# System.net
KiCad netlist of a schematic drawn in Altium Designer
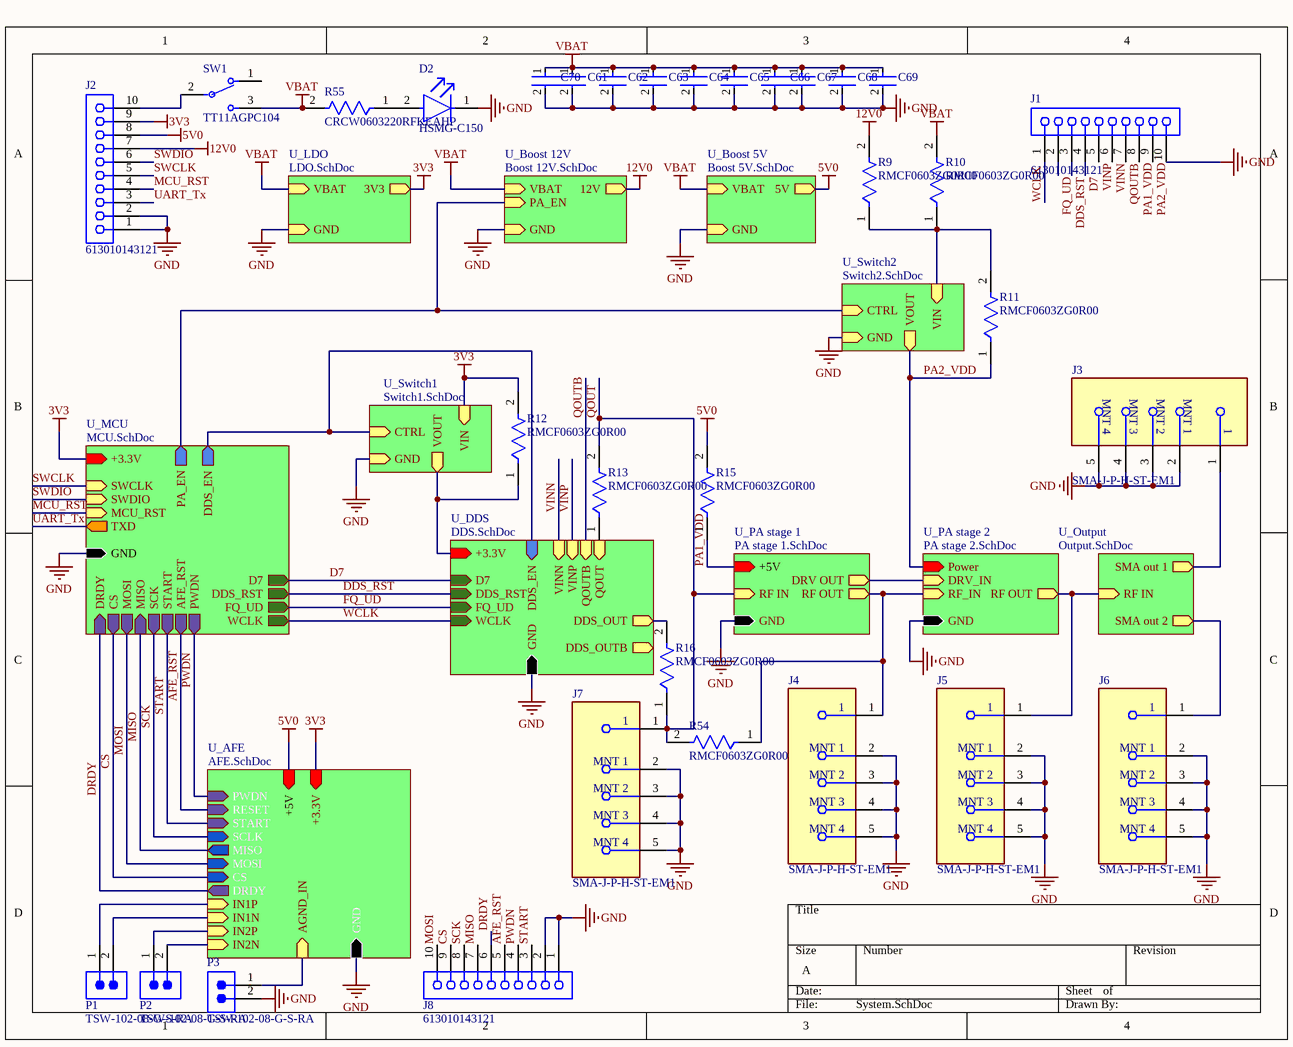
[diagram p0: System.SchDoc]

(export (version "E")
  (design (tool "Eeschema 10.0.6"))
  (components
    (comp (ref "C61")
      (value "GRM21BR60J107ME15K")
      (footprint "FP-GRM21B-0_2-e0_2_0_7-IPC_B")
      (description "Chip Multilayer Ceramic Capacitors for General Purpose, 0805, 100uF, X5R, 15%, 20%, 6.3V")
      (fields (field (name "TOLERANCE") "20%"))
      (libsource (lib "Altium Content Vault") (part "b4654b650e69147ec39a6b967a45e02"))
    )
    (comp (ref "C62")
      (value "GRM21BR60J107ME15K")
      (footprint "FP-GRM21B-0_2-e0_2_0_7-IPC_B")
      (description "Chip Multilayer Ceramic Capacitors for General Purpose, 0805, 100uF, X5R, 15%, 20%, 6.3V")
      (fields (field (name "TOLERANCE") "20%"))
      (libsource (lib "Altium Content Vault") (part "b4654b650e69147ec39a6b967a45e02"))
    )
    (comp (ref "C63")
      (value "GRM21BR60J107ME15K")
      (footprint "FP-GRM21B-0_2-e0_2_0_7-IPC_B")
      (description "Chip Multilayer Ceramic Capacitors for General Purpose, 0805, 100uF, X5R, 15%, 20%, 6.3V")
      (fields (field (name "TOLERANCE") "20%"))
      (libsource (lib "Altium Content Vault") (part "b4654b650e69147ec39a6b967a45e02"))
    )
    (comp (ref "C64")
      (value "GRM21BR60J107ME15K")
      (footprint "FP-GRM21B-0_2-e0_2_0_7-IPC_B")
      (description "Chip Multilayer Ceramic Capacitors for General Purpose, 0805, 100uF, X5R, 15%, 20%, 6.3V")
      (fields (field (name "TOLERANCE") "20%"))
      (libsource (lib "Altium Content Vault") (part "b4654b650e69147ec39a6b967a45e02"))
    )
    (comp (ref "C65")
      (value "GRM21BR60J107ME15K")
      (footprint "FP-GRM21B-0_2-e0_2_0_7-IPC_B")
      (description "Chip Multilayer Ceramic Capacitors for General Purpose, 0805, 100uF, X5R, 15%, 20%, 6.3V")
      (fields (field (name "TOLERANCE") "20%"))
      (libsource (lib "Altium Content Vault") (part "b4654b650e69147ec39a6b967a45e02"))
    )
    (comp (ref "C66")
      (value "GRM21BR60J107ME15K")
      (footprint "FP-GRM21B-0_2-e0_2_0_7-IPC_B")
      (description "Chip Multilayer Ceramic Capacitors for General Purpose, 0805, 100uF, X5R, 15%, 20%, 6.3V")
      (fields (field (name "TOLERANCE") "20%"))
      (libsource (lib "Altium Content Vault") (part "b4654b650e69147ec39a6b967a45e02"))
    )
    (comp (ref "C67")
      (value "GRM21BR60J107ME15K")
      (footprint "FP-GRM21B-0_2-e0_2_0_7-IPC_B")
      (description "Chip Multilayer Ceramic Capacitors for General Purpose, 0805, 100uF, X5R, 15%, 20%, 6.3V")
      (fields (field (name "TOLERANCE") "20%"))
      (libsource (lib "Altium Content Vault") (part "b4654b650e69147ec39a6b967a45e02"))
    )
    (comp (ref "C68")
      (value "GRM21BR60J107ME15K")
      (footprint "FP-GRM21B-0_2-e0_2_0_7-IPC_B")
      (description "Chip Multilayer Ceramic Capacitors for General Purpose, 0805, 100uF, X5R, 15%, 20%, 6.3V")
      (fields (field (name "TOLERANCE") "20%"))
      (libsource (lib "Altium Content Vault") (part "b4654b650e69147ec39a6b967a45e02"))
    )
    (comp (ref "C69")
      (value "GRM21BR60J107ME15K")
      (footprint "FP-GRM21B-0_2-e0_2_0_7-IPC_B")
      (description "Chip Multilayer Ceramic Capacitors for General Purpose, 0805, 100uF, X5R, 15%, 20%, 6.3V")
      (fields (field (name "TOLERANCE") "20%"))
      (libsource (lib "Altium Content Vault") (part "b4654b650e69147ec39a6b967a45e02"))
    )
    (comp (ref "C70")
      (value "GRM21BR60J107ME15K")
      (footprint "FP-GRM21B-0_2-e0_2_0_7-IPC_B")
      (description "Chip Multilayer Ceramic Capacitors for General Purpose, 0805, 100uF, X5R, 15%, 20%, 6.3V")
      (fields (field (name "TOLERANCE") "20%"))
      (libsource (lib "Altium Content Vault") (part "b4654b650e69147ec39a6b967a45e02"))
    )
    (comp (ref "D2")
      (value "HSMG-C150")
      (footprint "FP-HSMG-C150-MFG")
      (description "LED GREEN DIFFUSED 1206 SMD")
      (fields
        (field (name "MANUFACTURER") "Broadcom")
        (field (name "OCTOPART") "https://octopart.com/hsmg-c150-broadcom-71131304")
      )
      (libsource (lib "Altium Content Vault") (part "8706943c75ba83719d021d2fdc84c58"))
    )
    (comp (ref "J1")
      (value "613010143121")
      (footprint "613010143121")
      (libsource (lib "Altium Content Vault") (part "Header_Female_1R_10P"))
    )
    (comp (ref "J2")
      (value "613010143121")
      (footprint "613010143121")
      (libsource (lib "Altium Content Vault") (part "Header_Female_1R_10P"))
    )
    (comp (ref "J3")
      (value "SMA-J-P-H-ST-EM1")
      (footprint "FP-SMA-J-P-H-ST-EM1-MFG")
      (description "CONN SMA JACK STR 50OHM EDGE MNT")
      (libsource (lib "") (part "c65b8a639cdaef1819ea20b5466f8fa_1"))
    )
    (comp (ref "J4")
      (value "SMA-J-P-H-ST-EM1")
      (footprint "FP-SMA-J-P-H-ST-EM1-MFG")
      (description "CONN SMA JACK STR 50OHM EDGE MNT")
      (libsource (lib "Altium Content Vault") (part "c65b8a639cdaef1819ea20b5466f8fa"))
    )
    (comp (ref "J5")
      (value "SMA-J-P-H-ST-EM1")
      (footprint "FP-SMA-J-P-H-ST-EM1-MFG")
      (description "CONN SMA JACK STR 50OHM EDGE MNT")
      (libsource (lib "Altium Content Vault") (part "c65b8a639cdaef1819ea20b5466f8fa"))
    )
    (comp (ref "J6")
      (value "SMA-J-P-H-ST-EM1")
      (footprint "FP-SMA-J-P-H-ST-EM1-MFG")
      (description "CONN SMA JACK STR 50OHM EDGE MNT")
      (libsource (lib "Altium Content Vault") (part "c65b8a639cdaef1819ea20b5466f8fa"))
    )
    (comp (ref "J7")
      (value "SMA-J-P-H-ST-EM1")
      (footprint "FP-SMA-J-P-H-ST-EM1-MFG")
      (description "CONN SMA JACK STR 50OHM EDGE MNT")
      (libsource (lib "Altium Content Vault") (part "c65b8a639cdaef1819ea20b5466f8fa"))
    )
    (comp (ref "J8")
      (value "613010143121")
      (footprint "613010143121")
      (libsource (lib "Altium Content Vault") (part "Header_Female_1R_10P"))
    )
    (comp (ref "P1")
      (value "TSW-102-08-G-S-RA")
      (footprint "SMTC-TSW-102-08-X-S-RA")
      (fields (field (name "MANUFACTURER") "Samtec"))
      (libsource (lib "Altium Content Vault") (part "SMTC-TSW-102-X-X-S-X"))
    )
    (comp (ref "P2")
      (value "TSW-102-08-G-S-RA")
      (footprint "SMTC-TSW-102-08-X-S-RA")
      (fields (field (name "MANUFACTURER") "Samtec"))
      (libsource (lib "Altium Content Vault") (part "SMTC-TSW-102-X-X-S-X"))
    )
    (comp (ref "P3")
      (value "TSW-102-08-G-S-RA")
      (footprint "SMTC-TSW-102-08-X-S-RA")
      (fields (field (name "MANUFACTURER") "Samtec"))
      (libsource (lib "Altium Content Vault") (part "SMTC-TSW-102-X-X-S-X"))
    )
    (comp (ref "R9")
      (value "RMCF0603ZG0R00")
      (footprint "FP-RMCF0603-IPC_B")
      (description "0Ω ±0 0.1W 0603 Thick Film Chip Resistor AEC-Q200 compliant")
      (libsource (lib "Altium Content Vault") (part "1029c3af85768c4190bb7ad29bc67b5"))
    )
    (comp (ref "R10")
      (value "RMCF0603ZG0R00")
      (footprint "FP-RMCF0603-IPC_B")
      (description "0Ω ±0 0.1W 0603 Thick Film Chip Resistor AEC-Q200 compliant")
      (libsource (lib "Altium Content Vault") (part "1029c3af85768c4190bb7ad29bc67b5"))
    )
    (comp (ref "R11")
      (value "RMCF0603ZG0R00")
      (footprint "FP-RMCF0603-IPC_B")
      (description "0Ω ±0 0.1W 0603 Thick Film Chip Resistor AEC-Q200 compliant")
      (libsource (lib "Altium Content Vault") (part "1029c3af85768c4190bb7ad29bc67b5"))
    )
    (comp (ref "R12")
      (value "RMCF0603ZG0R00")
      (footprint "FP-RMCF0603-IPC_B")
      (description "0Ω ±0 0.1W 0603 Thick Film Chip Resistor AEC-Q200 compliant")
      (libsource (lib "Altium Content Vault") (part "1029c3af85768c4190bb7ad29bc67b5"))
    )
    (comp (ref "R13")
      (value "RMCF0603ZG0R00")
      (footprint "FP-RMCF0603-IPC_B")
      (description "0Ω ±0 0.1W 0603 Thick Film Chip Resistor AEC-Q200 compliant")
      (libsource (lib "Altium Content Vault") (part "1029c3af85768c4190bb7ad29bc67b5"))
    )
    (comp (ref "R15")
      (value "RMCF0603ZG0R00")
      (footprint "FP-RMCF0603-IPC_B")
      (description "0Ω ±0 0.1W 0603 Thick Film Chip Resistor AEC-Q200 compliant")
      (libsource (lib "Altium Content Vault") (part "1029c3af85768c4190bb7ad29bc67b5"))
    )
    (comp (ref "R16")
      (value "RMCF0603ZG0R00")
      (footprint "FP-RMCF0603-IPC_B")
      (description "0Ω ±0 0.1W 0603 Thick Film Chip Resistor AEC-Q200 compliant")
      (libsource (lib "Altium Content Vault") (part "1029c3af85768c4190bb7ad29bc67b5"))
    )
    (comp (ref "R54")
      (value "RMCF0603ZG0R00")
      (footprint "FP-RMCF0603-IPC_B")
      (description "0Ω ±0 0.1W 0603 Thick Film Chip Resistor AEC-Q200 compliant")
      (libsource (lib "Altium Content Vault") (part "1029c3af85768c4190bb7ad29bc67b5"))
    )
    (comp (ref "R55")
      (value "CRCW0603220RFKEAHP")
      (footprint "FP-CRCW0603-HPe3-IPC_A")
      (description "RES Thick Film, 220Ω, 1%, 0.33W, 100ppm/°C, 0603")
      (fields (field (name "TOLERANCE") "1%"))
      (libsource (lib "Altium Content Vault") (part "1029c3af85768c4190bb7ad29bc67b5"))
    )
    (comp (ref "SW1")
      (value "TT11AGPC104")
      (footprint "FP-TT11AGPC104-MFG")
      (description "SWITCH TOGGLE SPST 0.4VA 20V")
      (libsource (lib "Altium Content Vault") (part "52c419afdc2a387c7d548259a9aeefb"))
    )
  )
  (nets
    (net (code "1") (name "/AFE_RST") (class "Default")
      (node (ref "J8") (pin "5") (pinfunction "5_5") (pintype "passive"))
    )
    (net (code "2") (name "/AGND_IN") (class "Default")
      (node (ref "P3") (pin "1") (pinfunction "1_1") (pintype "passive"))
    )
    (net (code "3") (name "/CS") (class "Default")
      (node (ref "J8") (pin "9") (pinfunction "9_9") (pintype "passive"))
    )
    (net (code "4") (name "/D7") (class "Default")
      (node (ref "J1") (pin "4") (pinfunction "4_4") (pintype "passive"))
    )
    (net (code "6") (name "/DDS_OUT") (class "Default")
      (node (ref "R16") (pin "2") (pinfunction "2_2") (pintype "passive"))
    )
    (net (code "8") (name "/DDS_RST") (class "Default")
      (node (ref "J1") (pin "3") (pinfunction "3_3") (pintype "passive"))
    )
    (net (code "9") (name "/DRDY") (class "Default")
      (node (ref "J8") (pin "6") (pinfunction "6_6") (pintype "passive"))
    )
    (net (code "11") (name "/FQ_UD") (class "Default")
      (node (ref "J1") (pin "2") (pinfunction "2_2") (pintype "passive"))
    )
    (net (code "12") (name "/IN1N") (class "Default")
      (node (ref "P1") (pin "2") (pinfunction "2_2") (pintype "passive"))
    )
    (net (code "13") (name "/IN1P") (class "Default")
      (node (ref "P1") (pin "1") (pinfunction "1_1") (pintype "passive"))
    )
    (net (code "14") (name "/IN2N") (class "Default")
      (node (ref "P2") (pin "2") (pinfunction "2_2") (pintype "passive"))
    )
    (net (code "15") (name "/IN2P") (class "Default")
      (node (ref "P2") (pin "1") (pinfunction "1_1") (pintype "passive"))
    )
    (net (code "16") (name "/MCU_RST") (class "Default")
      (node (ref "J2") (pin "4") (pinfunction "4_4") (pintype "passive"))
    )
    (net (code "17") (name "/MISO") (class "Default")
      (node (ref "J8") (pin "7") (pinfunction "7_7") (pintype "passive"))
    )
    (net (code "18") (name "/MOSI") (class "Default")
      (node (ref "J8") (pin "10") (pinfunction "10_10") (pintype "passive"))
    )
    (net (code "19") (name "/PA1_VDD") (class "Default")
      (node (ref "J1") (pin "8") (pinfunction "8_8") (pintype "passive"))
      (node (ref "R15") (pin "1") (pinfunction "1_1") (pintype "passive"))
    )
    (net (code "20") (name "/PA2_VDD") (class "Default")
      (node (ref "J1") (pin "9") (pinfunction "9_9") (pintype "passive"))
      (node (ref "R11") (pin "1") (pinfunction "1_1") (pintype "passive"))
    )
    (net (code "22") (name "/PWDN") (class "Default")
      (node (ref "J8") (pin "4") (pinfunction "4_4") (pintype "passive"))
    )
    (net (code "23") (name "/QOUT") (class "Default")
      (node (ref "J7") (pin "1") (pinfunction "1_1") (pintype "passive"))
      (node (ref "R13") (pin "2") (pinfunction "2_2") (pintype "passive"))
      (node (ref "R16") (pin "1") (pinfunction "1_1") (pintype "passive"))
      (node (ref "R54") (pin "2") (pinfunction "2_2") (pintype "passive"))
    )
    (net (code "24") (name "/QOUTB") (class "Default")
      (node (ref "J1") (pin "7") (pinfunction "7_7") (pintype "passive"))
    )
    (net (code "25") (name "/QOUT_1") (class "Default")
      (node (ref "R13") (pin "1") (pinfunction "1_1") (pintype "passive"))
    )
    (net (code "26") (name "/RF OUT") (class "Default")
      (node (ref "J5") (pin "1") (pinfunction "1_1") (pintype "passive"))
    )
    (net (code "27") (name "/RF OUT_1") (class "Default")
      (node (ref "J4") (pin "1") (pinfunction "1_1") (pintype "passive"))
      (node (ref "R54") (pin "1") (pinfunction "1_1") (pintype "passive"))
    )
    (net (code "28") (name "/SCK") (class "Default")
      (node (ref "J8") (pin "8") (pinfunction "8_8") (pintype "passive"))
    )
    (net (code "29") (name "/SMA out 1") (class "Default")
      (node (ref "J3") (pin "1") (pinfunction "1_1") (pintype "passive"))
    )
    (net (code "30") (name "/SMA out 2") (class "Default")
      (node (ref "J6") (pin "1") (pinfunction "1_1") (pintype "passive"))
    )
    (net (code "31") (name "/START") (class "Default")
      (node (ref "J8") (pin "3") (pinfunction "3_3") (pintype "passive"))
    )
    (net (code "32") (name "/SWCLK") (class "Default")
      (node (ref "J2") (pin "5") (pinfunction "5_5") (pintype "passive"))
    )
    (net (code "33") (name "/SWDIO") (class "Default")
      (node (ref "J2") (pin "6") (pinfunction "6_6") (pintype "passive"))
    )
    (net (code "34") (name "/UART_Tx") (class "Default")
      (node (ref "J2") (pin "3") (pinfunction "3_3") (pintype "passive"))
    )
    (net (code "35") (name "/VIN") (class "Default")
      (node (ref "R10") (pin "1") (pinfunction "1_1") (pintype "passive"))
      (node (ref "R11") (pin "2") (pinfunction "2_2") (pintype "passive"))
      (node (ref "R9") (pin "1") (pinfunction "1_1") (pintype "passive"))
    )
    (net (code "36") (name "/VINN") (class "Default")
      (node (ref "J1") (pin "6") (pinfunction "6_6") (pintype "passive"))
    )
    (net (code "37") (name "/VINP") (class "Default")
      (node (ref "J1") (pin "5") (pinfunction "5_5") (pintype "passive"))
    )
    (net (code "38") (name "/VOUT") (class "Default")
      (node (ref "R12") (pin "1") (pinfunction "1_1") (pintype "passive"))
    )
    (net (code "39") (name "/WCLK") (class "Default")
      (node (ref "J1") (pin "1") (pinfunction "1_1") (pintype "passive"))
    )
    (net (code "40") (name "3V3") (class "Default")
      (node (ref "J2") (pin "9") (pinfunction "9_9") (pintype "passive"))
      (node (ref "R12") (pin "2") (pinfunction "2_2") (pintype "passive"))
    )
    (net (code "41") (name "5V0") (class "Default")
      (node (ref "J2") (pin "8") (pinfunction "8_8") (pintype "passive"))
      (node (ref "R15") (pin "2") (pinfunction "2_2") (pintype "passive"))
    )
    (net (code "42") (name "12V0") (class "Default")
      (node (ref "J2") (pin "7") (pinfunction "7_7") (pintype "passive"))
      (node (ref "R9") (pin "2") (pinfunction "2_2") (pintype "passive"))
    )
    (net (code "43") (name "GND") (class "Default")
      (node (ref "C61") (pin "2") (pinfunction "2_2") (pintype "passive"))
      (node (ref "C62") (pin "2") (pinfunction "2_2") (pintype "passive"))
      (node (ref "C63") (pin "2") (pinfunction "2_2") (pintype "passive"))
      (node (ref "C64") (pin "2") (pinfunction "2_2") (pintype "passive"))
      (node (ref "C65") (pin "2") (pinfunction "2_2") (pintype "passive"))
      (node (ref "C66") (pin "2") (pinfunction "2_2") (pintype "passive"))
      (node (ref "C67") (pin "2") (pinfunction "2_2") (pintype "passive"))
      (node (ref "C68") (pin "2") (pinfunction "2_2") (pintype "passive"))
      (node (ref "C69") (pin "2") (pinfunction "2_2") (pintype "passive"))
      (node (ref "C70") (pin "2") (pinfunction "2_2") (pintype "passive"))
      (node (ref "D2") (pin "1") (pinfunction "C_1") (pintype "passive"))
      (node (ref "J1") (pin "10") (pinfunction "10_10") (pintype "passive"))
      (node (ref "J2") (pin "1") (pinfunction "1_1") (pintype "passive"))
      (node (ref "J2") (pin "2") (pinfunction "2_2") (pintype "passive"))
      (node (ref "J3") (pin "2") (pinfunction "MNT_1_2") (pintype "passive"))
      (node (ref "J3") (pin "3") (pinfunction "MNT_2_3") (pintype "passive"))
      (node (ref "J3") (pin "4") (pinfunction "MNT_3_4") (pintype "passive"))
      (node (ref "J3") (pin "5") (pinfunction "MNT_4_5") (pintype "passive"))
      (node (ref "J4") (pin "2") (pinfunction "MNT_1_2") (pintype "passive"))
      (node (ref "J4") (pin "3") (pinfunction "MNT_2_3") (pintype "passive"))
      (node (ref "J4") (pin "4") (pinfunction "MNT_3_4") (pintype "passive"))
      (node (ref "J4") (pin "5") (pinfunction "MNT_4_5") (pintype "passive"))
      (node (ref "J5") (pin "2") (pinfunction "MNT_1_2") (pintype "passive"))
      (node (ref "J5") (pin "3") (pinfunction "MNT_2_3") (pintype "passive"))
      (node (ref "J5") (pin "4") (pinfunction "MNT_3_4") (pintype "passive"))
      (node (ref "J5") (pin "5") (pinfunction "MNT_4_5") (pintype "passive"))
      (node (ref "J6") (pin "2") (pinfunction "MNT_1_2") (pintype "passive"))
      (node (ref "J6") (pin "3") (pinfunction "MNT_2_3") (pintype "passive"))
      (node (ref "J6") (pin "4") (pinfunction "MNT_3_4") (pintype "passive"))
      (node (ref "J6") (pin "5") (pinfunction "MNT_4_5") (pintype "passive"))
      (node (ref "J7") (pin "2") (pinfunction "MNT_1_2") (pintype "passive"))
      (node (ref "J7") (pin "3") (pinfunction "MNT_2_3") (pintype "passive"))
      (node (ref "J7") (pin "4") (pinfunction "MNT_3_4") (pintype "passive"))
      (node (ref "J7") (pin "5") (pinfunction "MNT_4_5") (pintype "passive"))
      (node (ref "J8") (pin "1") (pinfunction "1_1") (pintype "passive"))
      (node (ref "J8") (pin "2") (pinfunction "2_2") (pintype "passive"))
      (node (ref "P3") (pin "2") (pinfunction "2_2") (pintype "passive"))
    )
    (net (code "44") (name "Net-(D2-A)") (class "Default")
      (node (ref "D2") (pin "2") (pinfunction "A_2") (pintype "passive"))
      (node (ref "R55") (pin "1") (pinfunction "1_1") (pintype "passive"))
    )
    (net (code "45") (name "Net-(J2-Pad10)") (class "Default")
      (node (ref "J2") (pin "10") (pinfunction "10_10") (pintype "passive"))
      (node (ref "SW1") (pin "2") (pinfunction "2_2") (pintype "passive"))
    )
    (net (code "46") (name "VBAT") (class "Default")
      (node (ref "C61") (pin "1") (pinfunction "1_1") (pintype "passive"))
      (node (ref "C62") (pin "1") (pinfunction "1_1") (pintype "passive"))
      (node (ref "C63") (pin "1") (pinfunction "1_1") (pintype "passive"))
      (node (ref "C64") (pin "1") (pinfunction "1_1") (pintype "passive"))
      (node (ref "C65") (pin "1") (pinfunction "1_1") (pintype "passive"))
      (node (ref "C66") (pin "1") (pinfunction "1_1") (pintype "passive"))
      (node (ref "C67") (pin "1") (pinfunction "1_1") (pintype "passive"))
      (node (ref "C68") (pin "1") (pinfunction "1_1") (pintype "passive"))
      (node (ref "C69") (pin "1") (pinfunction "1_1") (pintype "passive"))
      (node (ref "C70") (pin "1") (pinfunction "1_1") (pintype "passive"))
      (node (ref "R10") (pin "2") (pinfunction "2_2") (pintype "passive"))
      (node (ref "R55") (pin "2") (pinfunction "2_2") (pintype "passive"))
      (node (ref "SW1") (pin "3") (pinfunction "3_3") (pintype "passive"))
    )
    (net (code "47") (name "unconnected-(SW1-Pad1)") (class "Default")
      (node (ref "SW1") (pin "1") (pinfunction "1_1") (pintype "passive"))
    )
  )
)
